# 02_RNF24L01_PWM_BTN.net
KiCad netlist of a schematic drawn in Altium Designer
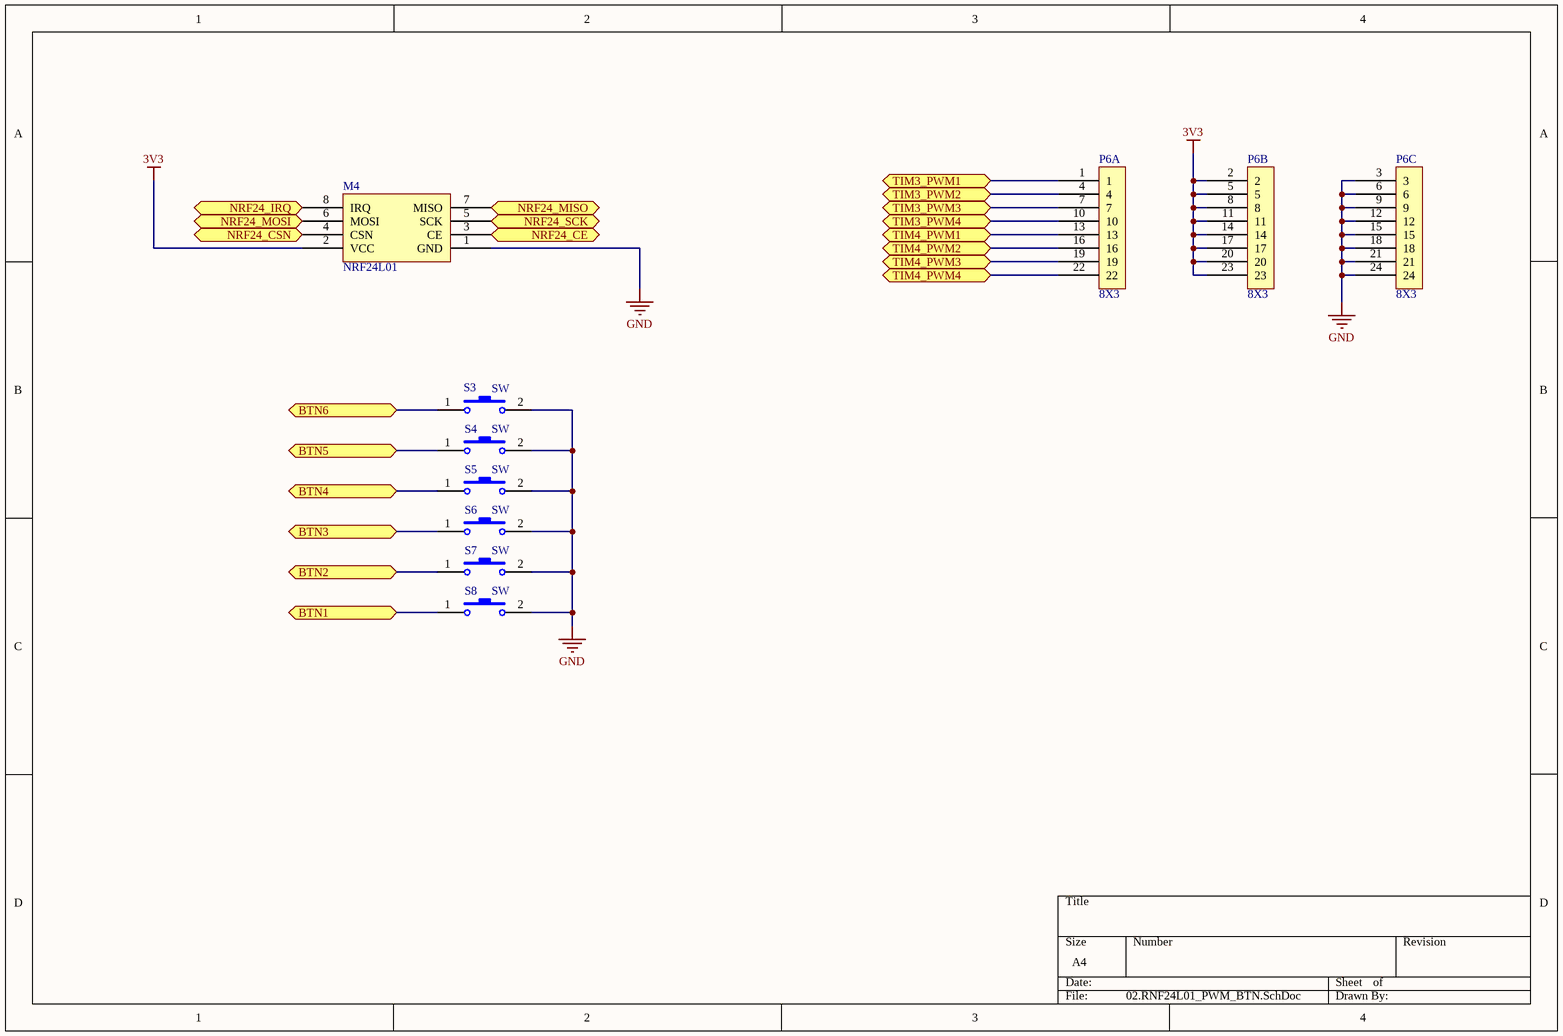
[diagram p0: 02.RNF24L01_PWM_BTN.SchDoc]

(export (version "E")
  (design (tool "Eeschema 10.0.6"))
  (components
    (comp (ref "M4")
      (value "NRF24L01")
      (footprint "HDR2X4")
      (libsource (lib "020.STM32F103RCT6_RNF24L01") (part "NRF24L01"))
    )
    (comp (ref "P6")
      (value "8X3")
      (footprint "HDR3X8-2.54")
      (libsource (lib "020.STM32F103RCT6_RNF24L01") (part "8X3"))
    )
    (comp (ref "S3")
      (value "SW")
      (footprint "SW4-6X6")
      (description "Switch")
      (fields (field (name "PUBLISHER") "Altium Limited"))
      (libsource (lib "YG_SCH_LIB") (part "SW"))
    )
    (comp (ref "S4")
      (value "SW")
      (footprint "SW4-6X6")
      (description "Switch")
      (fields (field (name "PUBLISHER") "Altium Limited"))
      (libsource (lib "YG_SCH_LIB") (part "SW"))
    )
    (comp (ref "S5")
      (value "SW")
      (footprint "SW4-6X6")
      (description "Switch")
      (fields (field (name "PUBLISHER") "Altium Limited"))
      (libsource (lib "YG_SCH_LIB") (part "SW"))
    )
    (comp (ref "S6")
      (value "SW")
      (footprint "SW4-6X6")
      (description "Switch")
      (fields (field (name "PUBLISHER") "Altium Limited"))
      (libsource (lib "YG_SCH_LIB") (part "SW"))
    )
    (comp (ref "S7")
      (value "SW")
      (footprint "SW4-6X6")
      (description "Switch")
      (fields (field (name "PUBLISHER") "Altium Limited"))
      (libsource (lib "YG_SCH_LIB") (part "SW"))
    )
    (comp (ref "S8")
      (value "SW")
      (footprint "SW4-6X6")
      (description "Switch")
      (fields (field (name "PUBLISHER") "Altium Limited"))
      (libsource (lib "YG_SCH_LIB") (part "SW"))
    )
  )
  (nets
    (net (code "1") (name "/BTN1") (class "Default")
      (node (ref "S8") (pin "1") (pinfunction "1_1") (pintype "passive"))
    )
    (net (code "2") (name "/BTN2") (class "Default")
      (node (ref "S7") (pin "1") (pinfunction "1_1") (pintype "passive"))
    )
    (net (code "3") (name "/BTN3") (class "Default")
      (node (ref "S6") (pin "1") (pinfunction "1_1") (pintype "passive"))
    )
    (net (code "4") (name "/BTN4") (class "Default")
      (node (ref "S5") (pin "1") (pinfunction "1_1") (pintype "passive"))
    )
    (net (code "5") (name "/BTN5") (class "Default")
      (node (ref "S4") (pin "1") (pinfunction "1_1") (pintype "passive"))
    )
    (net (code "6") (name "/BTN6") (class "Default")
      (node (ref "S3") (pin "1") (pinfunction "1_1") (pintype "passive"))
    )
    (net (code "7") (name "/NRF24_CE") (class "Default")
      (node (ref "M4") (pin "3") (pinfunction "CE_3") (pintype "passive"))
    )
    (net (code "8") (name "/NRF24_CSN") (class "Default")
      (node (ref "M4") (pin "4") (pinfunction "CSN_4") (pintype "passive"))
    )
    (net (code "9") (name "/NRF24_IRQ") (class "Default")
      (node (ref "M4") (pin "8") (pinfunction "IRQ_8") (pintype "passive"))
    )
    (net (code "10") (name "/NRF24_MISO") (class "Default")
      (node (ref "M4") (pin "7") (pinfunction "MISO_7") (pintype "passive"))
    )
    (net (code "11") (name "/NRF24_MOSI") (class "Default")
      (node (ref "M4") (pin "6") (pinfunction "MOSI_6") (pintype "passive"))
    )
    (net (code "12") (name "/NRF24_SCK") (class "Default")
      (node (ref "M4") (pin "5") (pinfunction "SCK_5") (pintype "passive"))
    )
    (net (code "13") (name "/TIM3_PWM1") (class "Default")
      (node (ref "P6") (pin "1") (pinfunction "1_1") (pintype "passive"))
    )
    (net (code "14") (name "/TIM3_PWM2") (class "Default")
      (node (ref "P6") (pin "4") (pinfunction "4_4") (pintype "passive"))
    )
    (net (code "15") (name "/TIM3_PWM3") (class "Default")
      (node (ref "P6") (pin "7") (pinfunction "7_7") (pintype "passive"))
    )
    (net (code "16") (name "/TIM3_PWM4") (class "Default")
      (node (ref "P6") (pin "10") (pinfunction "10_10") (pintype "passive"))
    )
    (net (code "17") (name "/TIM4_PWM1") (class "Default")
      (node (ref "P6") (pin "13") (pinfunction "13_13") (pintype "passive"))
    )
    (net (code "18") (name "/TIM4_PWM2") (class "Default")
      (node (ref "P6") (pin "16") (pinfunction "16_16") (pintype "passive"))
    )
    (net (code "19") (name "/TIM4_PWM3") (class "Default")
      (node (ref "P6") (pin "19") (pinfunction "19_19") (pintype "passive"))
    )
    (net (code "20") (name "/TIM4_PWM4") (class "Default")
      (node (ref "P6") (pin "22") (pinfunction "22_22") (pintype "passive"))
    )
    (net (code "21") (name "3V3") (class "Default")
      (node (ref "M4") (pin "2") (pinfunction "VCC_2") (pintype "passive"))
      (node (ref "P6") (pin "11") (pinfunction "11_11") (pintype "passive"))
      (node (ref "P6") (pin "14") (pinfunction "14_14") (pintype "passive"))
      (node (ref "P6") (pin "17") (pinfunction "17_17") (pintype "passive"))
      (node (ref "P6") (pin "2") (pinfunction "2_2") (pintype "passive"))
      (node (ref "P6") (pin "20") (pinfunction "20_20") (pintype "passive"))
      (node (ref "P6") (pin "23") (pinfunction "23_23") (pintype "passive"))
      (node (ref "P6") (pin "5") (pinfunction "5_5") (pintype "passive"))
      (node (ref "P6") (pin "8") (pinfunction "8_8") (pintype "passive"))
    )
    (net (code "22") (name "GND") (class "Default")
      (node (ref "M4") (pin "1") (pinfunction "GND_1") (pintype "passive"))
      (node (ref "P6") (pin "12") (pinfunction "12_12") (pintype "passive"))
      (node (ref "P6") (pin "15") (pinfunction "15_15") (pintype "passive"))
      (node (ref "P6") (pin "18") (pinfunction "18_18") (pintype "passive"))
      (node (ref "P6") (pin "21") (pinfunction "21_21") (pintype "passive"))
      (node (ref "P6") (pin "24") (pinfunction "24_24") (pintype "passive"))
      (node (ref "P6") (pin "3") (pinfunction "3_3") (pintype "passive"))
      (node (ref "P6") (pin "6") (pinfunction "6_6") (pintype "passive"))
      (node (ref "P6") (pin "9") (pinfunction "9_9") (pintype "passive"))
      (node (ref "S3") (pin "2") (pinfunction "2_2") (pintype "passive"))
      (node (ref "S4") (pin "2") (pinfunction "2_2") (pintype "passive"))
      (node (ref "S5") (pin "2") (pinfunction "2_2") (pintype "passive"))
      (node (ref "S6") (pin "2") (pinfunction "2_2") (pintype "passive"))
      (node (ref "S7") (pin "2") (pinfunction "2_2") (pintype "passive"))
      (node (ref "S8") (pin "2") (pinfunction "2_2") (pintype "passive"))
    )
  )
)
